# line_sensor.net
KiCad netlist of a schematic drawn in EAGLE
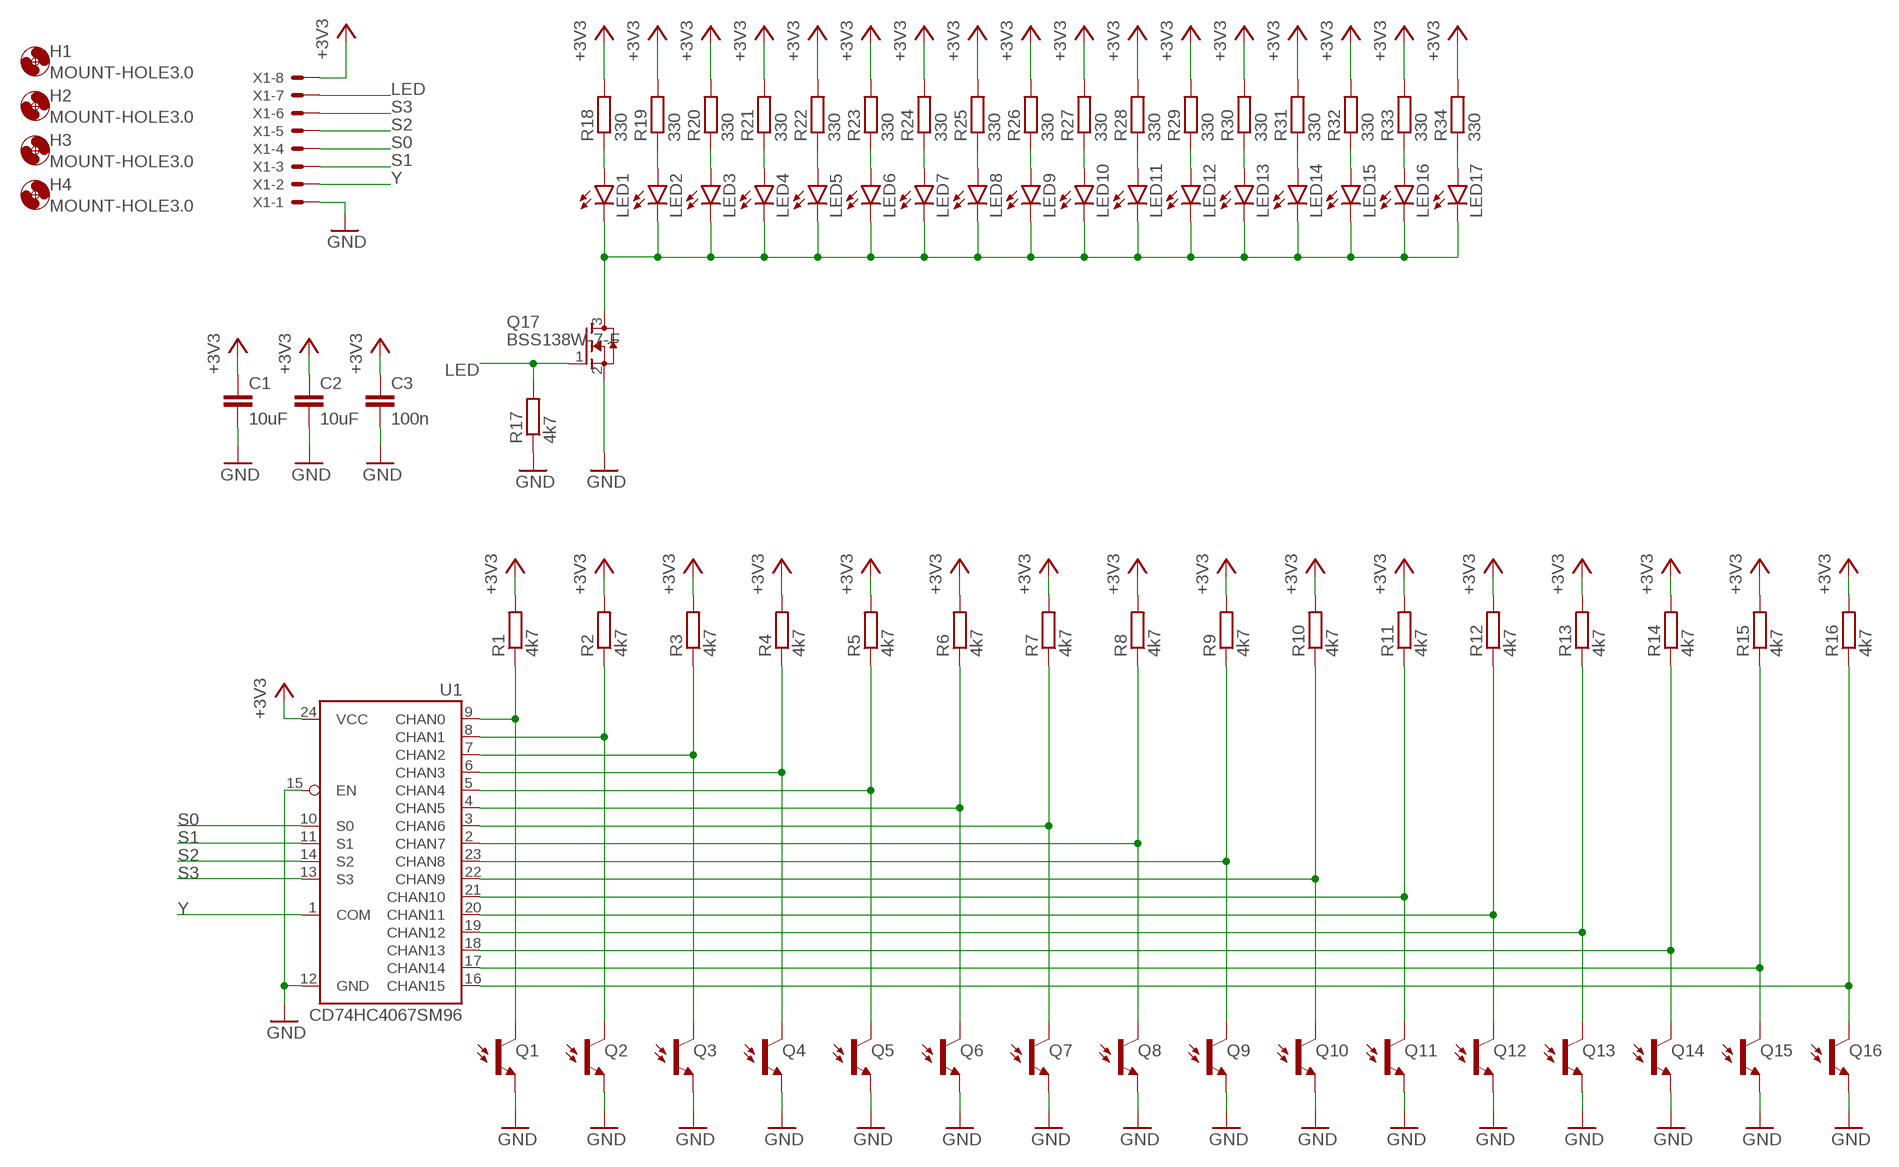
[diagram p0: schematic, sheet 1]

(export (version "E")
  (design (tool "Eeschema 10.0.6"))
  (components
    (comp (ref "C1")
      (value "10uF")
      (footprint "eagle-import:C0805")
      (libsource (lib "eagle-import") (part "C-EUC0805"))
    )
    (comp (ref "C2")
      (value "10uF")
      (footprint "eagle-import:C0805")
      (libsource (lib "eagle-import") (part "C-EUC0805"))
    )
    (comp (ref "C3")
      (value "100n")
      (footprint "eagle-import:C0805")
      (libsource (lib "eagle-import") (part "C-EUC0805"))
    )
    (comp (ref "H1")
      (value "MOUNT-HOLE3.0")
      (footprint "eagle-import:3,0")
      (libsource (lib "eagle-import") (part "MOUNT-HOLE3.0"))
    )
    (comp (ref "H2")
      (value "MOUNT-HOLE3.0")
      (footprint "eagle-import:3,0")
      (libsource (lib "eagle-import") (part "MOUNT-HOLE3.0"))
    )
    (comp (ref "H3")
      (value "MOUNT-HOLE3.0")
      (footprint "eagle-import:3,0")
      (libsource (lib "eagle-import") (part "MOUNT-HOLE3.0"))
    )
    (comp (ref "H4")
      (value "MOUNT-HOLE3.0")
      (footprint "eagle-import:3,0")
      (libsource (lib "eagle-import") (part "MOUNT-HOLE3.0"))
    )
    (comp (ref "LED1")
      (value "LEDSML1206")
      (footprint "eagle-import:SML1206")
      (libsource (lib "eagle-import") (part "LEDSML1206"))
    )
    (comp (ref "LED2")
      (value "LEDSML1206")
      (footprint "eagle-import:SML1206")
      (libsource (lib "eagle-import") (part "LEDSML1206"))
    )
    (comp (ref "LED3")
      (value "LEDSML1206")
      (footprint "eagle-import:SML1206")
      (libsource (lib "eagle-import") (part "LEDSML1206"))
    )
    (comp (ref "LED4")
      (value "LEDSML1206")
      (footprint "eagle-import:SML1206")
      (libsource (lib "eagle-import") (part "LEDSML1206"))
    )
    (comp (ref "LED5")
      (value "LEDSML1206")
      (footprint "eagle-import:SML1206")
      (libsource (lib "eagle-import") (part "LEDSML1206"))
    )
    (comp (ref "LED6")
      (value "LEDSML1206")
      (footprint "eagle-import:SML1206")
      (libsource (lib "eagle-import") (part "LEDSML1206"))
    )
    (comp (ref "LED7")
      (value "LEDSML1206")
      (footprint "eagle-import:SML1206")
      (libsource (lib "eagle-import") (part "LEDSML1206"))
    )
    (comp (ref "LED8")
      (value "LEDSML1206")
      (footprint "eagle-import:SML1206")
      (libsource (lib "eagle-import") (part "LEDSML1206"))
    )
    (comp (ref "LED9")
      (value "LEDSML1206")
      (footprint "eagle-import:SML1206")
      (libsource (lib "eagle-import") (part "LEDSML1206"))
    )
    (comp (ref "LED10")
      (value "LEDSML1206")
      (footprint "eagle-import:SML1206")
      (libsource (lib "eagle-import") (part "LEDSML1206"))
    )
    (comp (ref "LED11")
      (value "LEDSML1206")
      (footprint "eagle-import:SML1206")
      (libsource (lib "eagle-import") (part "LEDSML1206"))
    )
    (comp (ref "LED12")
      (value "LEDSML1206")
      (footprint "eagle-import:SML1206")
      (libsource (lib "eagle-import") (part "LEDSML1206"))
    )
    (comp (ref "LED13")
      (value "LEDSML1206")
      (footprint "eagle-import:SML1206")
      (libsource (lib "eagle-import") (part "LEDSML1206"))
    )
    (comp (ref "LED14")
      (value "LEDSML1206")
      (footprint "eagle-import:SML1206")
      (libsource (lib "eagle-import") (part "LEDSML1206"))
    )
    (comp (ref "LED15")
      (value "LEDSML1206")
      (footprint "eagle-import:SML1206")
      (libsource (lib "eagle-import") (part "LEDSML1206"))
    )
    (comp (ref "LED16")
      (value "LEDSML1206")
      (footprint "eagle-import:SML1206")
      (libsource (lib "eagle-import") (part "LEDSML1206"))
    )
    (comp (ref "LED17")
      (value "LEDSML1206")
      (footprint "eagle-import:SML1206")
      (libsource (lib "eagle-import") (part "LEDSML1206"))
    )
    (comp (ref "Q1")
      (value "20mA/30V")
      (footprint "eagle-import:PT17-21C-L41-TR8")
      (libsource (lib "eagle-import") (part "PHOTOTRANSISTORPT17-21C-L41-TR8"))
    )
    (comp (ref "Q2")
      (value "20mA/30V")
      (footprint "eagle-import:PT17-21C-L41-TR8")
      (libsource (lib "eagle-import") (part "PHOTOTRANSISTORPT17-21C-L41-TR8"))
    )
    (comp (ref "Q3")
      (value "20mA/30V")
      (footprint "eagle-import:PT17-21C-L41-TR8")
      (libsource (lib "eagle-import") (part "PHOTOTRANSISTORPT17-21C-L41-TR8"))
    )
    (comp (ref "Q4")
      (value "20mA/30V")
      (footprint "eagle-import:PT17-21C-L41-TR8")
      (libsource (lib "eagle-import") (part "PHOTOTRANSISTORPT17-21C-L41-TR8"))
    )
    (comp (ref "Q5")
      (value "20mA/30V")
      (footprint "eagle-import:PT17-21C-L41-TR8")
      (libsource (lib "eagle-import") (part "PHOTOTRANSISTORPT17-21C-L41-TR8"))
    )
    (comp (ref "Q6")
      (value "20mA/30V")
      (footprint "eagle-import:PT17-21C-L41-TR8")
      (libsource (lib "eagle-import") (part "PHOTOTRANSISTORPT17-21C-L41-TR8"))
    )
    (comp (ref "Q7")
      (value "20mA/30V")
      (footprint "eagle-import:PT17-21C-L41-TR8")
      (libsource (lib "eagle-import") (part "PHOTOTRANSISTORPT17-21C-L41-TR8"))
    )
    (comp (ref "Q8")
      (value "20mA/30V")
      (footprint "eagle-import:PT17-21C-L41-TR8")
      (libsource (lib "eagle-import") (part "PHOTOTRANSISTORPT17-21C-L41-TR8"))
    )
    (comp (ref "Q9")
      (value "20mA/30V")
      (footprint "eagle-import:PT17-21C-L41-TR8")
      (libsource (lib "eagle-import") (part "PHOTOTRANSISTORPT17-21C-L41-TR8"))
    )
    (comp (ref "Q10")
      (value "20mA/30V")
      (footprint "eagle-import:PT17-21C-L41-TR8")
      (libsource (lib "eagle-import") (part "PHOTOTRANSISTORPT17-21C-L41-TR8"))
    )
    (comp (ref "Q11")
      (value "20mA/30V")
      (footprint "eagle-import:PT17-21C-L41-TR8")
      (libsource (lib "eagle-import") (part "PHOTOTRANSISTORPT17-21C-L41-TR8"))
    )
    (comp (ref "Q12")
      (value "20mA/30V")
      (footprint "eagle-import:PT17-21C-L41-TR8")
      (libsource (lib "eagle-import") (part "PHOTOTRANSISTORPT17-21C-L41-TR8"))
    )
    (comp (ref "Q13")
      (value "20mA/30V")
      (footprint "eagle-import:PT17-21C-L41-TR8")
      (libsource (lib "eagle-import") (part "PHOTOTRANSISTORPT17-21C-L41-TR8"))
    )
    (comp (ref "Q14")
      (value "20mA/30V")
      (footprint "eagle-import:PT17-21C-L41-TR8")
      (libsource (lib "eagle-import") (part "PHOTOTRANSISTORPT17-21C-L41-TR8"))
    )
    (comp (ref "Q15")
      (value "20mA/30V")
      (footprint "eagle-import:PT17-21C-L41-TR8")
      (libsource (lib "eagle-import") (part "PHOTOTRANSISTORPT17-21C-L41-TR8"))
    )
    (comp (ref "Q16")
      (value "20mA/30V")
      (footprint "eagle-import:PT17-21C-L41-TR8")
      (libsource (lib "eagle-import") (part "PHOTOTRANSISTORPT17-21C-L41-TR8"))
    )
    (comp (ref "Q17")
      (value "BSS138W-7-F")
      (footprint "eagle-import:SOT323")
      (libsource (lib "eagle-import") (part "BSS138W-7-F"))
    )
    (comp (ref "R1")
      (value "4k7")
      (footprint "eagle-import:M0805")
      (libsource (lib "eagle-import") (part "R-EU_M0805"))
    )
    (comp (ref "R2")
      (value "4k7")
      (footprint "eagle-import:M0805")
      (libsource (lib "eagle-import") (part "R-EU_M0805"))
    )
    (comp (ref "R3")
      (value "4k7")
      (footprint "eagle-import:M0805")
      (libsource (lib "eagle-import") (part "R-EU_M0805"))
    )
    (comp (ref "R4")
      (value "4k7")
      (footprint "eagle-import:M0805")
      (libsource (lib "eagle-import") (part "R-EU_M0805"))
    )
    (comp (ref "R5")
      (value "4k7")
      (footprint "eagle-import:M0805")
      (libsource (lib "eagle-import") (part "R-EU_M0805"))
    )
    (comp (ref "R6")
      (value "4k7")
      (footprint "eagle-import:M0805")
      (libsource (lib "eagle-import") (part "R-EU_M0805"))
    )
    (comp (ref "R7")
      (value "4k7")
      (footprint "eagle-import:M0805")
      (libsource (lib "eagle-import") (part "R-EU_M0805"))
    )
    (comp (ref "R8")
      (value "4k7")
      (footprint "eagle-import:M0805")
      (libsource (lib "eagle-import") (part "R-EU_M0805"))
    )
    (comp (ref "R9")
      (value "4k7")
      (footprint "eagle-import:M0805")
      (libsource (lib "eagle-import") (part "R-EU_M0805"))
    )
    (comp (ref "R10")
      (value "4k7")
      (footprint "eagle-import:M0805")
      (libsource (lib "eagle-import") (part "R-EU_M0805"))
    )
    (comp (ref "R11")
      (value "4k7")
      (footprint "eagle-import:M0805")
      (libsource (lib "eagle-import") (part "R-EU_M0805"))
    )
    (comp (ref "R12")
      (value "4k7")
      (footprint "eagle-import:M0805")
      (libsource (lib "eagle-import") (part "R-EU_M0805"))
    )
    (comp (ref "R13")
      (value "4k7")
      (footprint "eagle-import:M0805")
      (libsource (lib "eagle-import") (part "R-EU_M0805"))
    )
    (comp (ref "R14")
      (value "4k7")
      (footprint "eagle-import:M0805")
      (libsource (lib "eagle-import") (part "R-EU_M0805"))
    )
    (comp (ref "R15")
      (value "4k7")
      (footprint "eagle-import:M0805")
      (libsource (lib "eagle-import") (part "R-EU_M0805"))
    )
    (comp (ref "R16")
      (value "4k7")
      (footprint "eagle-import:M0805")
      (libsource (lib "eagle-import") (part "R-EU_M0805"))
    )
    (comp (ref "R17")
      (value "4k7")
      (footprint "eagle-import:M0805")
      (libsource (lib "eagle-import") (part "R-EU_M0805"))
    )
    (comp (ref "R18")
      (value "330")
      (footprint "eagle-import:M0805")
      (libsource (lib "eagle-import") (part "R-EU_M0805"))
    )
    (comp (ref "R19")
      (value "330")
      (footprint "eagle-import:M0805")
      (libsource (lib "eagle-import") (part "R-EU_M0805"))
    )
    (comp (ref "R20")
      (value "330")
      (footprint "eagle-import:M0805")
      (libsource (lib "eagle-import") (part "R-EU_M0805"))
    )
    (comp (ref "R21")
      (value "330")
      (footprint "eagle-import:M0805")
      (libsource (lib "eagle-import") (part "R-EU_M0805"))
    )
    (comp (ref "R22")
      (value "330")
      (footprint "eagle-import:M0805")
      (libsource (lib "eagle-import") (part "R-EU_M0805"))
    )
    (comp (ref "R23")
      (value "330")
      (footprint "eagle-import:M0805")
      (libsource (lib "eagle-import") (part "R-EU_M0805"))
    )
    (comp (ref "R24")
      (value "330")
      (footprint "eagle-import:M0805")
      (libsource (lib "eagle-import") (part "R-EU_M0805"))
    )
    (comp (ref "R25")
      (value "330")
      (footprint "eagle-import:M0805")
      (libsource (lib "eagle-import") (part "R-EU_M0805"))
    )
    (comp (ref "R26")
      (value "330")
      (footprint "eagle-import:M0805")
      (libsource (lib "eagle-import") (part "R-EU_M0805"))
    )
    (comp (ref "R27")
      (value "330")
      (footprint "eagle-import:M0805")
      (libsource (lib "eagle-import") (part "R-EU_M0805"))
    )
    (comp (ref "R28")
      (value "330")
      (footprint "eagle-import:M0805")
      (libsource (lib "eagle-import") (part "R-EU_M0805"))
    )
    (comp (ref "R29")
      (value "330")
      (footprint "eagle-import:M0805")
      (libsource (lib "eagle-import") (part "R-EU_M0805"))
    )
    (comp (ref "R30")
      (value "330")
      (footprint "eagle-import:M0805")
      (libsource (lib "eagle-import") (part "R-EU_M0805"))
    )
    (comp (ref "R31")
      (value "330")
      (footprint "eagle-import:M0805")
      (libsource (lib "eagle-import") (part "R-EU_M0805"))
    )
    (comp (ref "R32")
      (value "330")
      (footprint "eagle-import:M0805")
      (libsource (lib "eagle-import") (part "R-EU_M0805"))
    )
    (comp (ref "R33")
      (value "330")
      (footprint "eagle-import:M0805")
      (libsource (lib "eagle-import") (part "R-EU_M0805"))
    )
    (comp (ref "R34")
      (value "330")
      (footprint "eagle-import:M0805")
      (libsource (lib "eagle-import") (part "R-EU_M0805"))
    )
    (comp (ref "U1")
      (value "CD74HC4067SM96")
      (footprint "eagle-import:SSOP24")
      (libsource (lib "eagle-import") (part "744067SM96HC"))
    )
    (comp (ref "X1")
      (value "52745-0890")
      (footprint "eagle-import:52745-0890")
      (fields (field (name "MF") "MOLEX"))
      (libsource (lib "eagle-import") (part "52745-0890"))
    )
  )
  (nets
    (net (code "1") (name "+3V3") (class "Default")
      (node (ref "C1") (pin "1") (pinfunction "1_1") (pintype "passive"))
      (node (ref "C2") (pin "1") (pinfunction "1_1") (pintype "passive"))
      (node (ref "C3") (pin "1") (pinfunction "1_1") (pintype "passive"))
      (node (ref "R1") (pin "2") (pinfunction "2_2") (pintype "passive"))
      (node (ref "R10") (pin "2") (pinfunction "2_2") (pintype "passive"))
      (node (ref "R11") (pin "2") (pinfunction "2_2") (pintype "passive"))
      (node (ref "R12") (pin "2") (pinfunction "2_2") (pintype "passive"))
      (node (ref "R13") (pin "2") (pinfunction "2_2") (pintype "passive"))
      (node (ref "R14") (pin "2") (pinfunction "2_2") (pintype "passive"))
      (node (ref "R15") (pin "2") (pinfunction "2_2") (pintype "passive"))
      (node (ref "R16") (pin "2") (pinfunction "2_2") (pintype "passive"))
      (node (ref "R18") (pin "2") (pinfunction "2_2") (pintype "passive"))
      (node (ref "R19") (pin "2") (pinfunction "2_2") (pintype "passive"))
      (node (ref "R2") (pin "2") (pinfunction "2_2") (pintype "passive"))
      (node (ref "R20") (pin "2") (pinfunction "2_2") (pintype "passive"))
      (node (ref "R21") (pin "2") (pinfunction "2_2") (pintype "passive"))
      (node (ref "R22") (pin "2") (pinfunction "2_2") (pintype "passive"))
      (node (ref "R23") (pin "2") (pinfunction "2_2") (pintype "passive"))
      (node (ref "R24") (pin "2") (pinfunction "2_2") (pintype "passive"))
      (node (ref "R25") (pin "2") (pinfunction "2_2") (pintype "passive"))
      (node (ref "R26") (pin "2") (pinfunction "2_2") (pintype "passive"))
      (node (ref "R27") (pin "2") (pinfunction "2_2") (pintype "passive"))
      (node (ref "R28") (pin "2") (pinfunction "2_2") (pintype "passive"))
      (node (ref "R29") (pin "2") (pinfunction "2_2") (pintype "passive"))
      (node (ref "R3") (pin "2") (pinfunction "2_2") (pintype "passive"))
      (node (ref "R30") (pin "2") (pinfunction "2_2") (pintype "passive"))
      (node (ref "R31") (pin "2") (pinfunction "2_2") (pintype "passive"))
      (node (ref "R32") (pin "2") (pinfunction "2_2") (pintype "passive"))
      (node (ref "R33") (pin "2") (pinfunction "2_2") (pintype "passive"))
      (node (ref "R34") (pin "2") (pinfunction "2_2") (pintype "passive"))
      (node (ref "R4") (pin "2") (pinfunction "2_2") (pintype "passive"))
      (node (ref "R5") (pin "2") (pinfunction "2_2") (pintype "passive"))
      (node (ref "R6") (pin "2") (pinfunction "2_2") (pintype "passive"))
      (node (ref "R7") (pin "2") (pinfunction "2_2") (pintype "passive"))
      (node (ref "R8") (pin "2") (pinfunction "2_2") (pintype "passive"))
      (node (ref "R9") (pin "2") (pinfunction "2_2") (pintype "passive"))
      (node (ref "U1") (pin "24") (pinfunction "VCC_24") (pintype "bidirectional"))
      (node (ref "X1") (pin "8") (pinfunction "S_8") (pintype "passive"))
    )
    (net (code "2") (name "/LED") (class "Default")
      (node (ref "Q17") (pin "1") (pinfunction "G_1") (pintype "passive"))
      (node (ref "R17") (pin "2") (pinfunction "2_2") (pintype "passive"))
      (node (ref "X1") (pin "7") (pinfunction "S_7") (pintype "passive"))
    )
    (net (code "3") (name "/S0") (class "Default")
      (node (ref "U1") (pin "10") (pinfunction "S0_10") (pintype "input"))
      (node (ref "X1") (pin "4") (pinfunction "S_4") (pintype "passive"))
    )
    (net (code "4") (name "/S1") (class "Default")
      (node (ref "U1") (pin "11") (pinfunction "S1_11") (pintype "input"))
      (node (ref "X1") (pin "3") (pinfunction "S_3") (pintype "passive"))
    )
    (net (code "5") (name "/S2") (class "Default")
      (node (ref "U1") (pin "14") (pinfunction "S2_14") (pintype "input"))
      (node (ref "X1") (pin "5") (pinfunction "S_5") (pintype "passive"))
    )
    (net (code "6") (name "/S3") (class "Default")
      (node (ref "U1") (pin "13") (pinfunction "S3_13") (pintype "input"))
      (node (ref "X1") (pin "6") (pinfunction "S_6") (pintype "passive"))
    )
    (net (code "7") (name "/Y") (class "Default")
      (node (ref "U1") (pin "1") (pinfunction "COM_1") (pintype "bidirectional"))
      (node (ref "X1") (pin "2") (pinfunction "S_2") (pintype "passive"))
    )
    (net (code "8") (name "GND") (class "Default")
      (node (ref "C1") (pin "2") (pinfunction "2_2") (pintype "passive"))
      (node (ref "C2") (pin "2") (pinfunction "2_2") (pintype "passive"))
      (node (ref "C3") (pin "2") (pinfunction "2_2") (pintype "passive"))
      (node (ref "Q1") (pin "E") (pinfunction "E_E") (pintype "passive"))
      (node (ref "Q10") (pin "E") (pinfunction "E_E") (pintype "passive"))
      (node (ref "Q11") (pin "E") (pinfunction "E_E") (pintype "passive"))
      (node (ref "Q12") (pin "E") (pinfunction "E_E") (pintype "passive"))
      (node (ref "Q13") (pin "E") (pinfunction "E_E") (pintype "passive"))
      (node (ref "Q14") (pin "E") (pinfunction "E_E") (pintype "passive"))
      (node (ref "Q15") (pin "E") (pinfunction "E_E") (pintype "passive"))
      (node (ref "Q16") (pin "E") (pinfunction "E_E") (pintype "passive"))
      (node (ref "Q17") (pin "2") (pinfunction "S_2") (pintype "passive"))
      (node (ref "Q2") (pin "E") (pinfunction "E_E") (pintype "passive"))
      (node (ref "Q3") (pin "E") (pinfunction "E_E") (pintype "passive"))
      (node (ref "Q4") (pin "E") (pinfunction "E_E") (pintype "passive"))
      (node (ref "Q5") (pin "E") (pinfunction "E_E") (pintype "passive"))
      (node (ref "Q6") (pin "E") (pinfunction "E_E") (pintype "passive"))
      (node (ref "Q7") (pin "E") (pinfunction "E_E") (pintype "passive"))
      (node (ref "Q8") (pin "E") (pinfunction "E_E") (pintype "passive"))
      (node (ref "Q9") (pin "E") (pinfunction "E_E") (pintype "passive"))
      (node (ref "R17") (pin "1") (pinfunction "1_1") (pintype "passive"))
      (node (ref "U1") (pin "12") (pinfunction "GND_12") (pintype "bidirectional"))
      (node (ref "U1") (pin "15") (pinfunction "EN_15") (pintype "input"))
      (node (ref "X1") (pin "1") (pinfunction "S_1") (pintype "passive"))
    )
    (net (code "9") (name "Net-(LED1-PadA)") (class "Default")
      (node (ref "LED1") (pin "A") (pinfunction "A_A") (pintype "passive"))
      (node (ref "R18") (pin "1") (pinfunction "1_1") (pintype "passive"))
    )
    (net (code "10") (name "Net-(LED2-PadA)") (class "Default")
      (node (ref "LED2") (pin "A") (pinfunction "A_A") (pintype "passive"))
      (node (ref "R19") (pin "1") (pinfunction "1_1") (pintype "passive"))
    )
    (net (code "11") (name "Net-(LED3-PadA)") (class "Default")
      (node (ref "LED3") (pin "A") (pinfunction "A_A") (pintype "passive"))
      (node (ref "R20") (pin "1") (pinfunction "1_1") (pintype "passive"))
    )
    (net (code "12") (name "Net-(LED4-PadA)") (class "Default")
      (node (ref "LED4") (pin "A") (pinfunction "A_A") (pintype "passive"))
      (node (ref "R21") (pin "1") (pinfunction "1_1") (pintype "passive"))
    )
    (net (code "13") (name "Net-(LED5-PadA)") (class "Default")
      (node (ref "LED5") (pin "A") (pinfunction "A_A") (pintype "passive"))
      (node (ref "R22") (pin "1") (pinfunction "1_1") (pintype "passive"))
    )
    (net (code "14") (name "Net-(LED6-PadA)") (class "Default")
      (node (ref "LED6") (pin "A") (pinfunction "A_A") (pintype "passive"))
      (node (ref "R23") (pin "1") (pinfunction "1_1") (pintype "passive"))
    )
    (net (code "15") (name "Net-(LED7-PadA)") (class "Default")
      (node (ref "LED7") (pin "A") (pinfunction "A_A") (pintype "passive"))
      (node (ref "R24") (pin "1") (pinfunction "1_1") (pintype "passive"))
    )
    (net (code "16") (name "Net-(LED8-PadA)") (class "Default")
      (node (ref "LED8") (pin "A") (pinfunction "A_A") (pintype "passive"))
      (node (ref "R25") (pin "1") (pinfunction "1_1") (pintype "passive"))
    )
    (net (code "17") (name "Net-(LED9-PadA)") (class "Default")
      (node (ref "LED9") (pin "A") (pinfunction "A_A") (pintype "passive"))
      (node (ref "R26") (pin "1") (pinfunction "1_1") (pintype "passive"))
    )
    (net (code "18") (name "Net-(LED10-PadA)") (class "Default")
      (node (ref "LED10") (pin "A") (pinfunction "A_A") (pintype "passive"))
      (node (ref "R27") (pin "1") (pinfunction "1_1") (pintype "passive"))
    )
    (net (code "19") (name "Net-(LED11-PadA)") (class "Default")
      (node (ref "LED11") (pin "A") (pinfunction "A_A") (pintype "passive"))
      (node (ref "R28") (pin "1") (pinfunction "1_1") (pintype "passive"))
    )
    (net (code "20") (name "Net-(LED12-PadA)") (class "Default")
      (node (ref "LED12") (pin "A") (pinfunction "A_A") (pintype "passive"))
      (node (ref "R29") (pin "1") (pinfunction "1_1") (pintype "passive"))
    )
    (net (code "21") (name "Net-(LED13-PadA)") (class "Default")
      (node (ref "LED13") (pin "A") (pinfunction "A_A") (pintype "passive"))
      (node (ref "R30") (pin "1") (pinfunction "1_1") (pintype "passive"))
    )
    (net (code "22") (name "Net-(LED14-PadA)") (class "Default")
      (node (ref "LED14") (pin "A") (pinfunction "A_A") (pintype "passive"))
      (node (ref "R31") (pin "1") (pinfunction "1_1") (pintype "passive"))
    )
    (net (code "23") (name "Net-(LED15-PadA)") (class "Default")
      (node (ref "LED15") (pin "A") (pinfunction "A_A") (pintype "passive"))
      (node (ref "R32") (pin "1") (pinfunction "1_1") (pintype "passive"))
    )
    (net (code "24") (name "Net-(LED16-PadA)") (class "Default")
      (node (ref "LED16") (pin "A") (pinfunction "A_A") (pintype "passive"))
      (node (ref "R33") (pin "1") (pinfunction "1_1") (pintype "passive"))
    )
    (net (code "25") (name "Net-(LED17-PadA)") (class "Default")
      (node (ref "LED17") (pin "A") (pinfunction "A_A") (pintype "passive"))
      (node (ref "R34") (pin "1") (pinfunction "1_1") (pintype "passive"))
    )
    (net (code "26") (name "Net-(Q17-D)") (class "Default")
      (node (ref "LED1") (pin "C") (pinfunction "C_C") (pintype "passive"))
      (node (ref "LED10") (pin "C") (pinfunction "C_C") (pintype "passive"))
      (node (ref "LED11") (pin "C") (pinfunction "C_C") (pintype "passive"))
      (node (ref "LED12") (pin "C") (pinfunction "C_C") (pintype "passive"))
      (node (ref "LED13") (pin "C") (pinfunction "C_C") (pintype "passive"))
      (node (ref "LED14") (pin "C") (pinfunction "C_C") (pintype "passive"))
      (node (ref "LED15") (pin "C") (pinfunction "C_C") (pintype "passive"))
      (node (ref "LED16") (pin "C") (pinfunction "C_C") (pintype "passive"))
      (node (ref "LED17") (pin "C") (pinfunction "C_C") (pintype "passive"))
      (node (ref "LED2") (pin "C") (pinfunction "C_C") (pintype "passive"))
      (node (ref "LED3") (pin "C") (pinfunction "C_C") (pintype "passive"))
      (node (ref "LED4") (pin "C") (pinfunction "C_C") (pintype "passive"))
      (node (ref "LED5") (pin "C") (pinfunction "C_C") (pintype "passive"))
      (node (ref "LED6") (pin "C") (pinfunction "C_C") (pintype "passive"))
      (node (ref "LED7") (pin "C") (pinfunction "C_C") (pintype "passive"))
      (node (ref "LED8") (pin "C") (pinfunction "C_C") (pintype "passive"))
      (node (ref "LED9") (pin "C") (pinfunction "C_C") (pintype "passive"))
      (node (ref "Q17") (pin "3") (pinfunction "D_3") (pintype "passive"))
    )
    (net (code "27") (name "Net-(U1-CHAN0)") (class "Default")
      (node (ref "Q1") (pin "C") (pinfunction "C_C") (pintype "passive"))
      (node (ref "R1") (pin "1") (pinfunction "1_1") (pintype "passive"))
      (node (ref "U1") (pin "9") (pinfunction "CHAN0_9") (pintype "bidirectional"))
    )
    (net (code "28") (name "Net-(U1-CHAN1)") (class "Default")
      (node (ref "Q2") (pin "C") (pinfunction "C_C") (pintype "passive"))
      (node (ref "R2") (pin "1") (pinfunction "1_1") (pintype "passive"))
      (node (ref "U1") (pin "8") (pinfunction "CHAN1_8") (pintype "bidirectional"))
    )
    (net (code "29") (name "Net-(U1-CHAN2)") (class "Default")
      (node (ref "Q3") (pin "C") (pinfunction "C_C") (pintype "passive"))
      (node (ref "R3") (pin "1") (pinfunction "1_1") (pintype "passive"))
      (node (ref "U1") (pin "7") (pinfunction "CHAN2_7") (pintype "bidirectional"))
    )
    (net (code "30") (name "Net-(U1-CHAN3)") (class "Default")
      (node (ref "Q4") (pin "C") (pinfunction "C_C") (pintype "passive"))
      (node (ref "R4") (pin "1") (pinfunction "1_1") (pintype "passive"))
      (node (ref "U1") (pin "6") (pinfunction "CHAN3_6") (pintype "bidirectional"))
    )
    (net (code "31") (name "Net-(U1-CHAN4)") (class "Default")
      (node (ref "Q5") (pin "C") (pinfunction "C_C") (pintype "passive"))
      (node (ref "R5") (pin "1") (pinfunction "1_1") (pintype "passive"))
      (node (ref "U1") (pin "5") (pinfunction "CHAN4_5") (pintype "bidirectional"))
    )
    (net (code "32") (name "Net-(U1-CHAN5)") (class "Default")
      (node (ref "Q6") (pin "C") (pinfunction "C_C") (pintype "passive"))
      (node (ref "R6") (pin "1") (pinfunction "1_1") (pintype "passive"))
      (node (ref "U1") (pin "4") (pinfunction "CHAN5_4") (pintype "bidirectional"))
    )
    (net (code "33") (name "Net-(U1-CHAN6)") (class "Default")
      (node (ref "Q7") (pin "C") (pinfunction "C_C") (pintype "passive"))
      (node (ref "R7") (pin "1") (pinfunction "1_1") (pintype "passive"))
      (node (ref "U1") (pin "3") (pinfunction "CHAN6_3") (pintype "bidirectional"))
    )
    (net (code "34") (name "Net-(U1-CHAN7)") (class "Default")
      (node (ref "Q8") (pin "C") (pinfunction "C_C") (pintype "passive"))
      (node (ref "R8") (pin "1") (pinfunction "1_1") (pintype "passive"))
      (node (ref "U1") (pin "2") (pinfunction "CHAN7_2") (pintype "bidirectional"))
    )
    (net (code "35") (name "Net-(U1-CHAN8)") (class "Default")
      (node (ref "Q9") (pin "C") (pinfunction "C_C") (pintype "passive"))
      (node (ref "R9") (pin "1") (pinfunction "1_1") (pintype "passive"))
      (node (ref "U1") (pin "23") (pinfunction "CHAN8_23") (pintype "bidirectional"))
    )
    (net (code "36") (name "Net-(U1-CHAN9)") (class "Default")
      (node (ref "Q10") (pin "C") (pinfunction "C_C") (pintype "passive"))
      (node (ref "R10") (pin "1") (pinfunction "1_1") (pintype "passive"))
      (node (ref "U1") (pin "22") (pinfunction "CHAN9_22") (pintype "bidirectional"))
    )
    (net (code "37") (name "Net-(U1-CHAN10)") (class "Default")
      (node (ref "Q11") (pin "C") (pinfunction "C_C") (pintype "passive"))
      (node (ref "R11") (pin "1") (pinfunction "1_1") (pintype "passive"))
      (node (ref "U1") (pin "21") (pinfunction "CHAN10_21") (pintype "bidirectional"))
    )
    (net (code "38") (name "Net-(U1-CHAN11)") (class "Default")
      (node (ref "Q12") (pin "C") (pinfunction "C_C") (pintype "passive"))
      (node (ref "R12") (pin "1") (pinfunction "1_1") (pintype "passive"))
      (node (ref "U1") (pin "20") (pinfunction "CHAN11_20") (pintype "bidirectional"))
    )
    (net (code "39") (name "Net-(U1-CHAN12)") (class "Default")
      (node (ref "Q13") (pin "C") (pinfunction "C_C") (pintype "passive"))
      (node (ref "R13") (pin "1") (pinfunction "1_1") (pintype "passive"))
      (node (ref "U1") (pin "19") (pinfunction "CHAN12_19") (pintype "bidirectional"))
    )
    (net (code "40") (name "Net-(U1-CHAN13)") (class "Default")
      (node (ref "Q14") (pin "C") (pinfunction "C_C") (pintype "passive"))
      (node (ref "R14") (pin "1") (pinfunction "1_1") (pintype "passive"))
      (node (ref "U1") (pin "18") (pinfunction "CHAN13_18") (pintype "bidirectional"))
    )
    (net (code "41") (name "Net-(U1-CHAN14)") (class "Default")
      (node (ref "Q15") (pin "C") (pinfunction "C_C") (pintype "passive"))
      (node (ref "R15") (pin "1") (pinfunction "1_1") (pintype "passive"))
      (node (ref "U1") (pin "17") (pinfunction "CHAN14_17") (pintype "bidirectional"))
    )
    (net (code "42") (name "Net-(U1-CHAN15)") (class "Default")
      (node (ref "Q16") (pin "C") (pinfunction "C_C") (pintype "passive"))
      (node (ref "R16") (pin "1") (pinfunction "1_1") (pintype "passive"))
      (node (ref "U1") (pin "16") (pinfunction "CHAN15_16") (pintype "bidirectional"))
    )
  )
)
